# top_level.net
KiCad netlist of a schematic drawn in Altium Designer
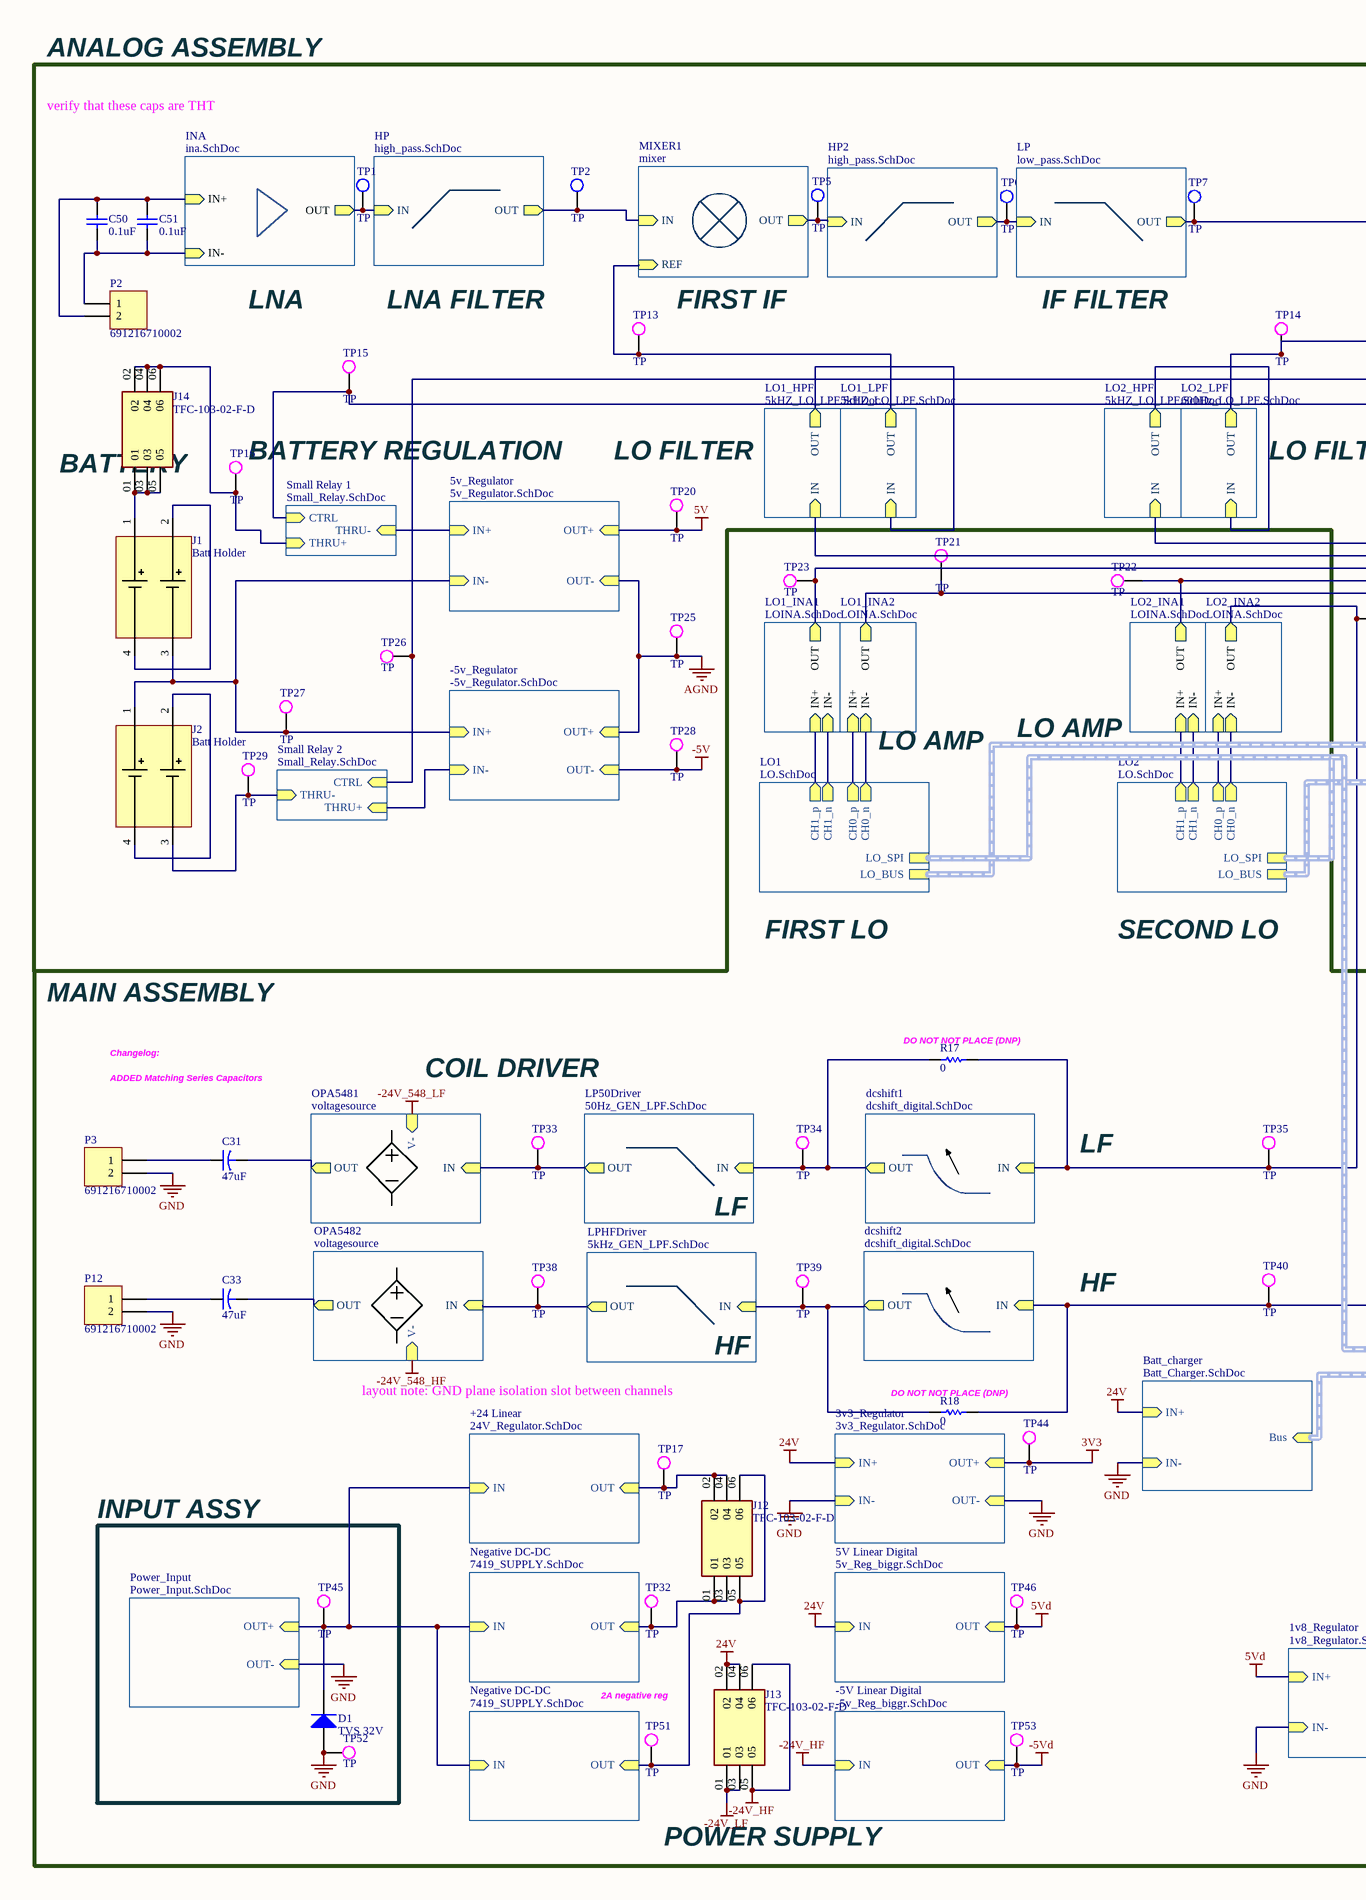
[diagram p0: top_level.SchDoc, left]
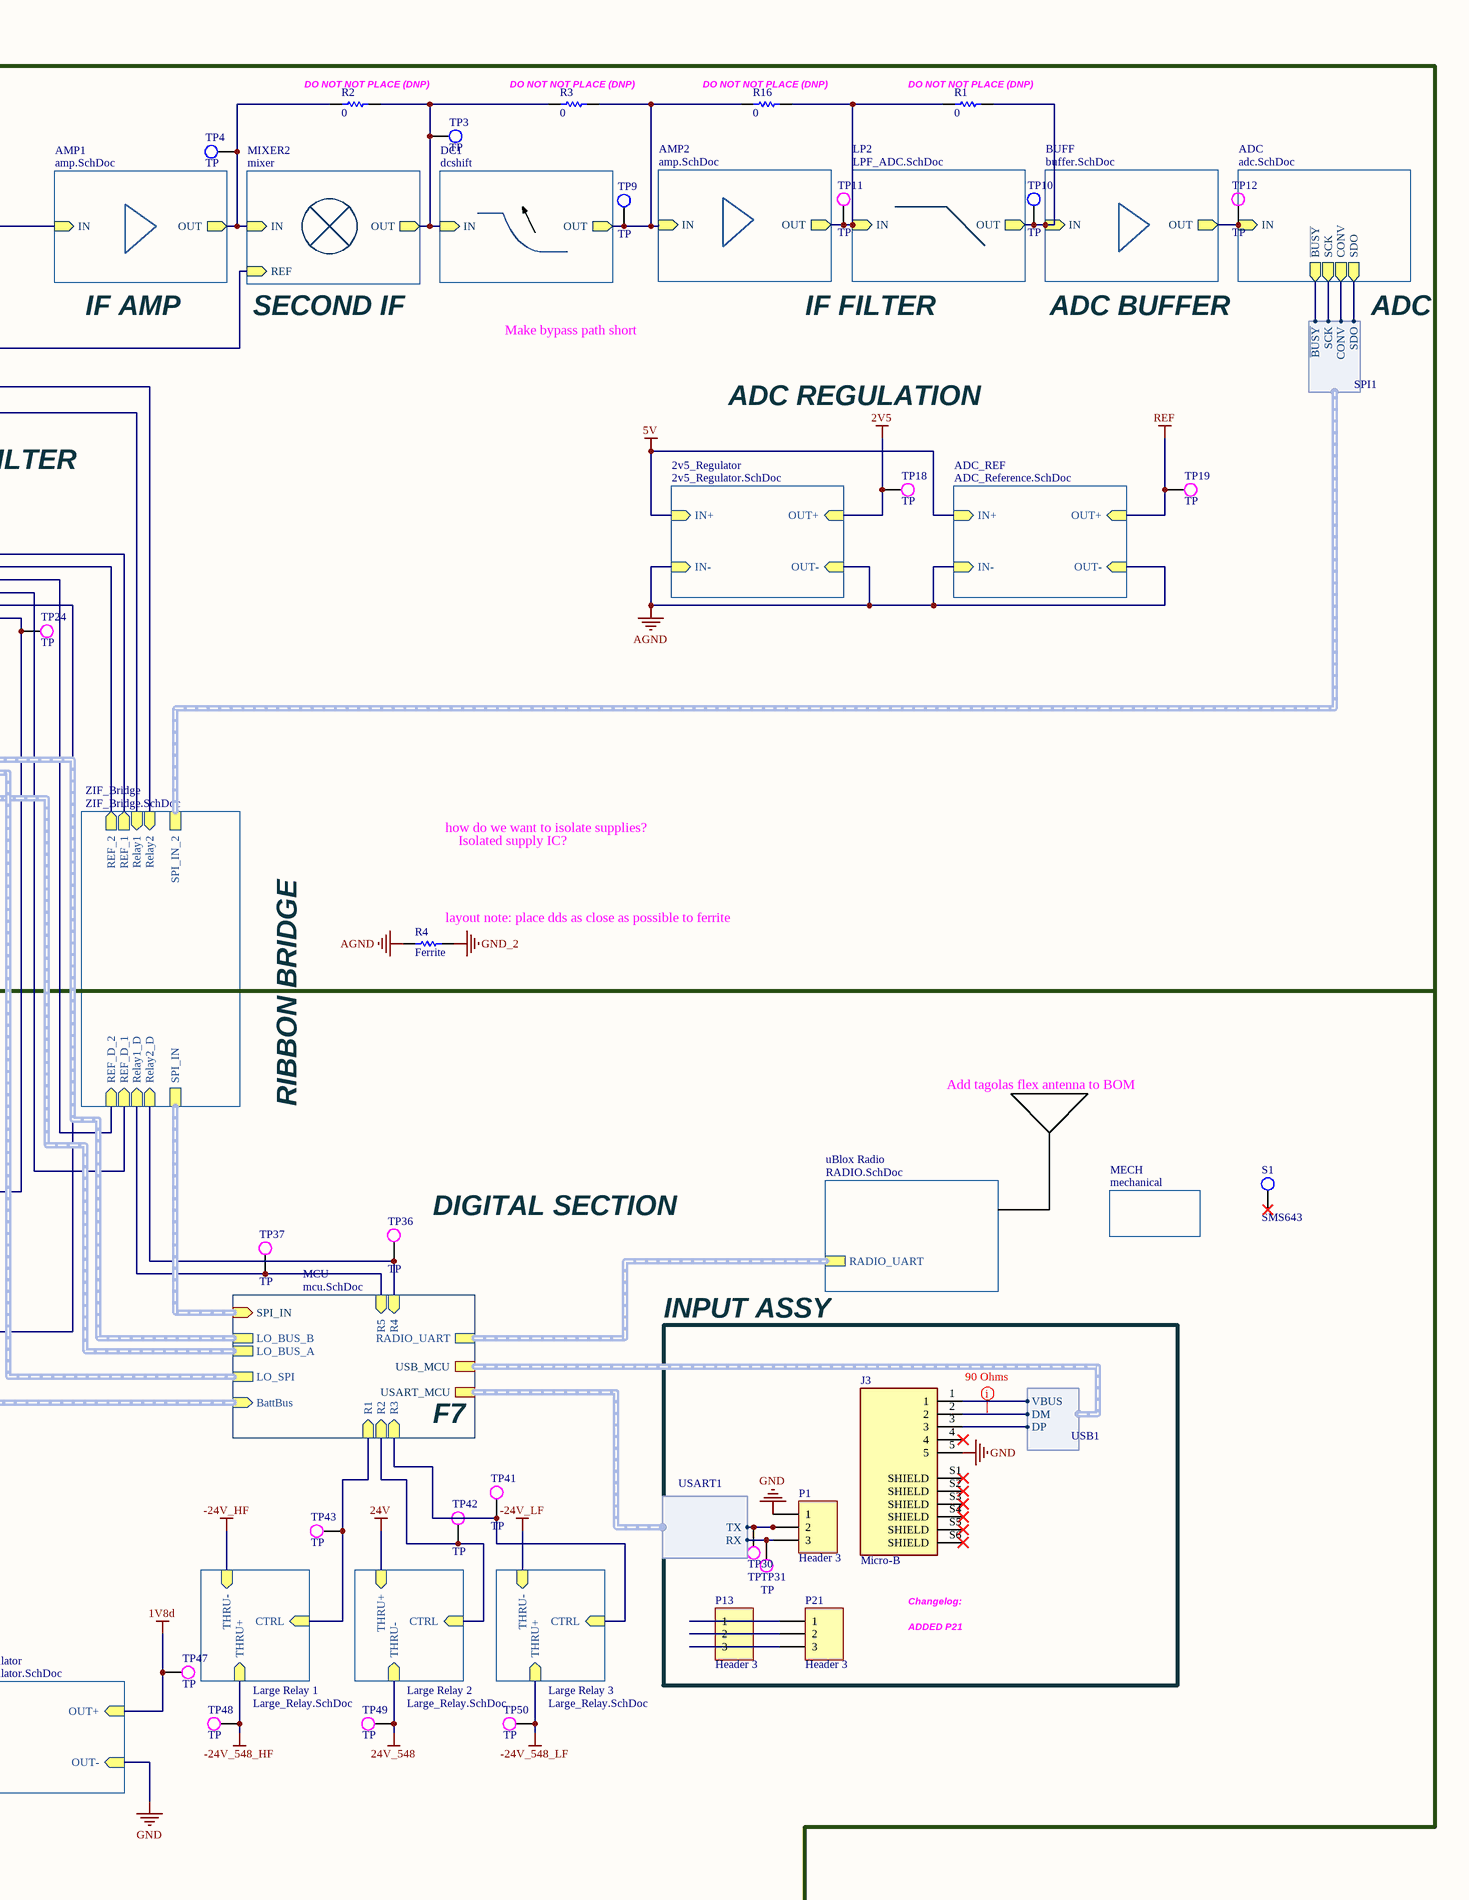
[diagram p1: top_level.SchDoc, right]

(export (version "E")
  (design (tool "Eeschema 10.0.6"))
  (components
    (comp (ref "C31")
      (value "47uF")
      (footprint "R60xW")
      (description "Capacitor, 47uF NICHICON")
      (libsource (lib "Arturo_Approved") (part "UCY2C470MPD"))
    )
    (comp (ref "C33")
      (value "47uF")
      (footprint "10uF_THT_Ceramic")
      (description "Capacitor, 47uF NICHICON")
      (libsource (lib "Arturo_Approved") (part "UCY2C470MPD"))
    )
    (comp (ref "C50")
      (value "0.1uF")
      (footprint "STD_0805_C")
      (description "Capacitor, 0.1uF, 0805")
      (libsource (lib "Arturo_Approved") (part "CL21B104KACNNNC"))
    )
    (comp (ref "C51")
      (value "0.1uF")
      (footprint "STD_0805_C")
      (description "Capacitor, 0.1uF, 0805")
      (libsource (lib "Arturo_Approved") (part "CL21B104KACNNNC"))
    )
    (comp (ref "D1")
      (value "TVS 32V")
      (footprint "TVSDIODE-DO214AA")
      (description "Default Diode")
      (fields (field (name "PUBLISHER") "Altium Limited"))
      (libsource (lib "Miscellaneous Devices") (part "Diode"))
    )
    (comp (ref "J1")
      (value "Batt Holder")
      (footprint "SMD_Batteryholder")
      (libsource (lib "Arturo_Approved") (part "1048_Keystone_18650"))
    )
    (comp (ref "J2")
      (value "Batt Holder")
      (footprint "SMD_Batteryholder")
      (libsource (lib "Arturo_Approved") (part "1048_Keystone_18650"))
    )
    (comp (ref "J3")
      (value "Micro-B")
      (footprint "10118194-0001LF")
      (description "USB - micro B USB 2.0 Receptacle Connector 5 Position Surface Mount, Right Angle; Through Hole")
      (libsource (lib "Arturo_Approved") (part "10118194-0001LF"))
    )
    (comp (ref "J12")
      (value "TFC-103-02-F-D")
      (footprint "Arturo_Approved:SAMTEC_TFC-103-02-F-D")
      (fields (field (name "MF") "Samtec"))
      (libsource (lib "Arturo_Approved") (part "TFC-103-02-F-D"))
    )
    (comp (ref "J13")
      (value "TFC-103-02-F-D")
      (footprint "Arturo_Approved:SAMTEC_TFC-103-02-F-D")
      (fields (field (name "MF") "Samtec"))
      (libsource (lib "Arturo_Approved") (part "TFC-103-02-F-D"))
    )
    (comp (ref "J14")
      (value "TFC-103-02-F-D")
      (footprint "Arturo_Approved:SAMTEC_TFC-103-02-F-D")
      (fields (field (name "MF") "Samtec"))
      (libsource (lib "Arturo_Approved") (part "TFC-103-02-F-D"))
    )
    (comp (ref "P1")
      (value "Header 3")
      (footprint "HDR1X3")
      (description "Header, 3-Pin")
      (fields (field (name "PUBLISHER") "Altium Limited"))
      (libsource (lib "Miscellaneous Connectors") (part "Header 3"))
    )
    (comp (ref "P2")
      (value "691216710002")
      (footprint "HDR1X2")
      (description "Header, 2-Pin")
      (fields (field (name "PUBLISHER") "Altium Limited"))
      (libsource (lib "") (part "Header 2_1"))
    )
    (comp (ref "P3")
      (value "691216710002")
      (footprint "HDR1X2")
      (description "Header, 2-Pin")
      (fields (field (name "PUBLISHER") "Altium Limited"))
      (libsource (lib "Miscellaneous Connectors") (part "Header 2"))
    )
    (comp (ref "P12")
      (value "691216710002")
      (footprint "HDR1X2")
      (description "Header, 2-Pin")
      (fields (field (name "PUBLISHER") "Altium Limited"))
      (libsource (lib "Miscellaneous Connectors") (part "Header 2"))
    )
    (comp (ref "P13")
      (value "Header 3")
      (footprint "HDR1X3")
      (description "Header, 3-Pin")
      (fields (field (name "PUBLISHER") "Altium Limited"))
      (libsource (lib "Miscellaneous Connectors") (part "Header 3"))
    )
    (comp (ref "P21")
      (value "Header 3")
      (footprint "HDR1X3")
      (description "Header, 3-Pin")
      (fields (field (name "PUBLISHER") "Altium Limited"))
      (libsource (lib "Miscellaneous Connectors") (part "Header 3"))
    )
    (comp (ref "R1")
      (value "0")
      (footprint "0402_Res")
      (description "0 ohm jumper")
      (libsource (lib "Arturo_Approved") (part "RMCF0805ZT0R00"))
    )
    (comp (ref "R2")
      (value "0")
      (footprint "0402_Res")
      (description "0 ohm jumper")
      (libsource (lib "Arturo_Approved") (part "RMCF0805ZT0R00"))
    )
    (comp (ref "R3")
      (value "0")
      (footprint "0402_Res")
      (description "0 ohm jumper")
      (libsource (lib "Arturo_Approved") (part "RMCF0805ZT0R00"))
    )
    (comp (ref "R4")
      (value "Ferrite")
      (footprint "0402_Res")
      (description "Ferrite 0805")
      (libsource (lib "Arturo_Approved") (part "BMB2A0600AN4"))
    )
    (comp (ref "R16")
      (value "0")
      (footprint "0402_Res")
      (description "0 ohm jumper")
      (libsource (lib "Arturo_Approved") (part "RMCF0805ZT0R00"))
    )
    (comp (ref "R17")
      (value "0")
      (footprint "0402_Res")
      (description "0 ohm jumper")
      (libsource (lib "Arturo_Approved") (part "RMCF0805ZT0R00"))
    )
    (comp (ref "R18")
      (value "0")
      (footprint "0402_Res")
      (description "0 ohm jumper")
      (libsource (lib "Arturo_Approved") (part "RMCF0805ZT0R00"))
    )
    (comp (ref "S1")
      (value "SMS643")
      (footprint "SMS-463F")
      (libsource (lib "Arturo_Approved") (part "SMS643"))
    )
    (comp (ref "TP1")
      (value "TP")
      (footprint "Test_point")
      (description "Test Point")
      (libsource (lib "Arturo_Approved") (part "TP"))
    )
    (comp (ref "TP2")
      (value "TP")
      (footprint "Test_point")
      (description "Test Point")
      (libsource (lib "Arturo_Approved") (part "TP"))
    )
    (comp (ref "TP3")
      (value "TP")
      (footprint "Test_point")
      (description "Test Point")
      (libsource (lib "Arturo_Approved") (part "TP"))
    )
    (comp (ref "TP4")
      (value "TP")
      (footprint "Test_point")
      (description "Test Point")
      (libsource (lib "Arturo_Approved") (part "TP"))
    )
    (comp (ref "TP5")
      (value "TP")
      (footprint "Test_point")
      (description "Test Point")
      (libsource (lib "Arturo_Approved") (part "TP"))
    )
    (comp (ref "TP6")
      (value "TP")
      (footprint "Test_point")
      (description "Test Point")
      (libsource (lib "Arturo_Approved") (part "TP"))
    )
    (comp (ref "TP7")
      (value "TP")
      (footprint "Test_point")
      (description "Test Point")
      (libsource (lib "Arturo_Approved") (part "TP"))
    )
    (comp (ref "TP9")
      (value "TP")
      (footprint "Test_point")
      (description "Test Point")
      (libsource (lib "Arturo_Approved") (part "TP"))
    )
    (comp (ref "TP10")
      (value "TP")
      (footprint "Test_point")
      (description "Test Point")
      (libsource (lib "Arturo_Approved") (part "TP"))
    )
    (comp (ref "TP11")
      (value "TP")
      (footprint "Test_point")
      (description "Test Point")
      (libsource (lib "Arturo_Approved") (part "TP_PCB"))
    )
    (comp (ref "TP12")
      (value "TP")
      (footprint "Test_point")
      (description "Test Point")
      (libsource (lib "Arturo_Approved") (part "TP_PCB"))
    )
    (comp (ref "TP13")
      (value "TP")
      (footprint "Test_point")
      (description "Test Point")
      (libsource (lib "Arturo_Approved") (part "TP_PCB"))
    )
    (comp (ref "TP14")
      (value "TP")
      (footprint "Test_point")
      (description "Test Point")
      (libsource (lib "Arturo_Approved") (part "TP_PCB"))
    )
    (comp (ref "TP15")
      (value "TP")
      (footprint "Test_point")
      (description "Test Point")
      (libsource (lib "Arturo_Approved") (part "TP_PCB"))
    )
    (comp (ref "TP16")
      (value "TP")
      (footprint "Test_point")
      (description "Test Point")
      (libsource (lib "Arturo_Approved") (part "TP_PCB"))
    )
    (comp (ref "TP17")
      (value "TP")
      (footprint "Test_point")
      (description "Test Point")
      (libsource (lib "Arturo_Approved") (part "TP_PCB"))
    )
    (comp (ref "TP18")
      (value "TP")
      (footprint "Test_point")
      (description "Test Point")
      (libsource (lib "Arturo_Approved") (part "TP_PCB"))
    )
    (comp (ref "TP19")
      (value "TP")
      (footprint "Test_point")
      (description "Test Point")
      (libsource (lib "Arturo_Approved") (part "TP_PCB"))
    )
    (comp (ref "TP20")
      (value "TP")
      (footprint "Test_point")
      (description "Test Point")
      (libsource (lib "Arturo_Approved") (part "TP_PCB"))
    )
    (comp (ref "TP21")
      (value "TP")
      (footprint "Test_point")
      (description "Test Point")
      (libsource (lib "Arturo_Approved") (part "TP_PCB"))
    )
    (comp (ref "TP22")
      (value "TP")
      (footprint "Test_point")
      (description "Test Point")
      (libsource (lib "Arturo_Approved") (part "TP_PCB"))
    )
    (comp (ref "TP23")
      (value "TP")
      (footprint "Test_point")
      (description "Test Point")
      (libsource (lib "Arturo_Approved") (part "TP_PCB"))
    )
    (comp (ref "TP24")
      (value "TP")
      (footprint "Test_point")
      (description "Test Point")
      (libsource (lib "Arturo_Approved") (part "TP_PCB"))
    )
    (comp (ref "TP25")
      (value "TP")
      (footprint "Test_point")
      (description "Test Point")
      (libsource (lib "Arturo_Approved") (part "TP_PCB"))
    )
    (comp (ref "TP26")
      (value "TP")
      (footprint "Test_point")
      (description "Test Point")
      (libsource (lib "Arturo_Approved") (part "TP_PCB"))
    )
    (comp (ref "TP27")
      (value "TP")
      (footprint "Test_point")
      (description "Test Point")
      (libsource (lib "Arturo_Approved") (part "TP_PCB"))
    )
    (comp (ref "TP28")
      (value "TP")
      (footprint "Test_point")
      (description "Test Point")
      (libsource (lib "Arturo_Approved") (part "TP_PCB"))
    )
    (comp (ref "TP29")
      (value "TP")
      (footprint "Test_point")
      (description "Test Point")
      (libsource (lib "Arturo_Approved") (part "TP_PCB"))
    )
    (comp (ref "TP30")
      (value "TP")
      (footprint "Test_point")
      (description "Test Point")
      (libsource (lib "Arturo_Approved") (part "TP_PCB"))
    )
    (comp (ref "TP31")
      (value "TP")
      (footprint "Test_point")
      (description "Test Point")
      (libsource (lib "Arturo_Approved") (part "TP_PCB"))
    )
    (comp (ref "TP32")
      (value "TP")
      (footprint "Test_point")
      (description "Test Point")
      (libsource (lib "Arturo_Approved") (part "TP_PCB"))
    )
    (comp (ref "TP33")
      (value "TP")
      (footprint "Test_point")
      (description "Test Point")
      (libsource (lib "Arturo_Approved") (part "TP_PCB"))
    )
    (comp (ref "TP34")
      (value "TP")
      (footprint "Test_point")
      (description "Test Point")
      (libsource (lib "Arturo_Approved") (part "TP_PCB"))
    )
    (comp (ref "TP35")
      (value "TP")
      (footprint "Test_point")
      (description "Test Point")
      (libsource (lib "Arturo_Approved") (part "TP_PCB"))
    )
    (comp (ref "TP36")
      (value "TP")
      (footprint "Test_point")
      (description "Test Point")
      (libsource (lib "Arturo_Approved") (part "TP_PCB"))
    )
    (comp (ref "TP37")
      (value "TP")
      (footprint "Test_point")
      (description "Test Point")
      (libsource (lib "Arturo_Approved") (part "TP_PCB"))
    )
    (comp (ref "TP38")
      (value "TP")
      (footprint "Test_point")
      (description "Test Point")
      (libsource (lib "Arturo_Approved") (part "TP_PCB"))
    )
    (comp (ref "TP39")
      (value "TP")
      (footprint "Test_point")
      (description "Test Point")
      (libsource (lib "Arturo_Approved") (part "TP_PCB"))
    )
    (comp (ref "TP40")
      (value "TP")
      (footprint "Test_point")
      (description "Test Point")
      (libsource (lib "Arturo_Approved") (part "TP_PCB"))
    )
    (comp (ref "TP41")
      (value "TP")
      (footprint "Test_point")
      (description "Test Point")
      (libsource (lib "Arturo_Approved") (part "TP_PCB"))
    )
    (comp (ref "TP42")
      (value "TP")
      (footprint "Test_point")
      (description "Test Point")
      (libsource (lib "Arturo_Approved") (part "TP_PCB"))
    )
    (comp (ref "TP43")
      (value "TP")
      (footprint "Test_point")
      (description "Test Point")
      (libsource (lib "Arturo_Approved") (part "TP_PCB"))
    )
    (comp (ref "TP44")
      (value "TP")
      (footprint "Test_point")
      (description "Test Point")
      (libsource (lib "Arturo_Approved") (part "TP_PCB"))
    )
    (comp (ref "TP45")
      (value "TP")
      (footprint "Test_point")
      (description "Test Point")
      (libsource (lib "Arturo_Approved") (part "TP_PCB"))
    )
    (comp (ref "TP46")
      (value "TP")
      (footprint "Test_point")
      (description "Test Point")
      (libsource (lib "Arturo_Approved") (part "TP_PCB"))
    )
    (comp (ref "TP47")
      (value "TP")
      (footprint "Test_point")
      (description "Test Point")
      (libsource (lib "Arturo_Approved") (part "TP_PCB"))
    )
    (comp (ref "TP48")
      (value "TP")
      (footprint "Test_point")
      (description "Test Point")
      (libsource (lib "Arturo_Approved") (part "TP_PCB"))
    )
    (comp (ref "TP49")
      (value "TP")
      (footprint "Test_point")
      (description "Test Point")
      (libsource (lib "Arturo_Approved") (part "TP_PCB"))
    )
    (comp (ref "TP50")
      (value "TP")
      (footprint "Test_point")
      (description "Test Point")
      (libsource (lib "Arturo_Approved") (part "TP_PCB"))
    )
    (comp (ref "TP51")
      (value "TP")
      (footprint "Test_point")
      (description "Test Point")
      (libsource (lib "Arturo_Approved") (part "TP_PCB"))
    )
    (comp (ref "TP52")
      (value "TP")
      (footprint "Test_point")
      (description "Test Point")
      (libsource (lib "Arturo_Approved") (part "TP_PCB"))
    )
    (comp (ref "TP53")
      (value "TP")
      (footprint "Test_point")
      (description "Test Point")
      (libsource (lib "Arturo_Approved") (part "TP_PCB"))
    )
  )
  (nets
    (net (code "4") (name "-5V") (class "Default")
      (node (ref "TP28") (pin "1") (pinfunction "1_1") (pintype "passive"))
    )
    (net (code "5") (name "-5Vd") (class "Default")
      (node (ref "TP53") (pin "1") (pinfunction "1_1") (pintype "passive"))
    )
    (net (code "6") (name "-24V_548_HF") (class "Default")
      (node (ref "TP48") (pin "1") (pinfunction "1_1") (pintype "passive"))
    )
    (net (code "7") (name "-24V_548_LF") (class "Default")
      (node (ref "TP50") (pin "1") (pinfunction "1_1") (pintype "passive"))
    )
    (net (code "8") (name "-24V_HF") (class "Default")
      (node (ref "J13") (pin "05") (pinfunction "05_05") (pintype "passive"))
      (node (ref "J13") (pin "06") (pinfunction "06_06") (pintype "passive"))
    )
    (net (code "9") (name "-24V_LF") (class "Default")
      (node (ref "J13") (pin "01") (pinfunction "01_01") (pintype "passive"))
      (node (ref "J13") (pin "03") (pinfunction "03_03") (pintype "passive"))
    )
    (net (code "20") (name "/CTRL") (class "Default")
      (node (ref "TP26") (pin "1") (pinfunction "1_1") (pintype "passive"))
    )
    (net (code "21") (name "/CTRL_1") (class "Default")
      (node (ref "TP43") (pin "1") (pinfunction "1_1") (pintype "passive"))
    )
    (net (code "22") (name "/CTRL_2") (class "Default")
      (node (ref "TP42") (pin "1") (pinfunction "1_1") (pintype "passive"))
    )
    (net (code "23") (name "/CTRL_3") (class "Default")
      (node (ref "TP41") (pin "1") (pinfunction "1_1") (pintype "passive"))
    )
    (net (code "24") (name "/CTRL_4") (class "Default")
      (node (ref "TP15") (pin "1") (pinfunction "1_1") (pintype "passive"))
    )
    (net (code "25") (name "/IN") (class "Default")
      (node (ref "D1") (pin "2") (pinfunction "K_2") (pintype "passive"))
      (node (ref "TP45") (pin "1") (pinfunction "1_1") (pintype "passive"))
    )
    (net (code "27") (name "/IN+_1") (class "Default")
      (node (ref "C50") (pin "2") (pinfunction "2_2") (pintype "passive"))
      (node (ref "C51") (pin "2") (pinfunction "2_2") (pintype "passive"))
      (node (ref "P2") (pin "2") (pinfunction "2_2") (pintype "passive"))
    )
    (net (code "28") (name "/IN+_2") (class "Default")
      (node (ref "J1") (pin "3") (pinfunction "3_3") (pintype "passive"))
      (node (ref "J2") (pin "1") (pinfunction "1_1") (pintype "passive"))
      (node (ref "TP27") (pin "1") (pinfunction "1_1") (pintype "passive"))
    )
    (net (code "30") (name "/IN-_1") (class "Default")
      (node (ref "C50") (pin "1") (pinfunction "1_1") (pintype "passive"))
      (node (ref "C51") (pin "1") (pinfunction "1_1") (pintype "passive"))
      (node (ref "P2") (pin "1") (pinfunction "1_1") (pintype "passive"))
    )
    (net (code "34") (name "/OUT") (class "Default")
      (node (ref "R1") (pin "2") (pinfunction "2_2") (pintype "passive"))
      (node (ref "TP10") (pin "1") (pinfunction "1_1") (pintype "passive"))
    )
    (net (code "35") (name "/OUT_1") (class "Default")
      (node (ref "R2") (pin "1") (pinfunction "1_1") (pintype "passive"))
      (node (ref "TP4") (pin "1") (pinfunction "1_1") (pintype "passive"))
    )
    (net (code "36") (name "/OUT_2") (class "Default")
      (node (ref "R2") (pin "2") (pinfunction "2_2") (pintype "passive"))
      (node (ref "R3") (pin "1") (pinfunction "1_1") (pintype "passive"))
      (node (ref "TP3") (pin "1") (pinfunction "1_1") (pintype "passive"))
    )
    (net (code "37") (name "/OUT_3") (class "Default")
      (node (ref "R16") (pin "1") (pinfunction "1_1") (pintype "passive"))
      (node (ref "R3") (pin "2") (pinfunction "2_2") (pintype "passive"))
      (node (ref "TP9") (pin "1") (pinfunction "1_1") (pintype "passive"))
    )
    (net (code "38") (name "/OUT_4") (class "Default")
      (node (ref "TP23") (pin "1") (pinfunction "1_1") (pintype "passive"))
    )
    (net (code "39") (name "/OUT_5") (class "Default")
      (node (ref "R17") (pin "2") (pinfunction "2_2") (pintype "passive"))
      (node (ref "TP24") (pin "1") (pinfunction "1_1") (pintype "passive"))
      (node (ref "TP35") (pin "1") (pinfunction "1_1") (pintype "passive"))
    )
    (net (code "40") (name "/OUT_6") (class "Default")
      (node (ref "TP22") (pin "1") (pinfunction "1_1") (pintype "passive"))
    )
    (net (code "41") (name "/OUT_7") (class "Default")
      (node (ref "R18") (pin "2") (pinfunction "2_2") (pintype "passive"))
      (node (ref "TP21") (pin "1") (pinfunction "1_1") (pintype "passive"))
      (node (ref "TP40") (pin "1") (pinfunction "1_1") (pintype "passive"))
    )
    (net (code "42") (name "/OUT_8") (class "Default")
      (node (ref "R17") (pin "1") (pinfunction "1_1") (pintype "passive"))
      (node (ref "TP34") (pin "1") (pinfunction "1_1") (pintype "passive"))
    )
    (net (code "43") (name "/OUT_9") (class "Default")
      (node (ref "R18") (pin "1") (pinfunction "1_1") (pintype "passive"))
      (node (ref "TP39") (pin "1") (pinfunction "1_1") (pintype "passive"))
    )
    (net (code "44") (name "/OUT_10") (class "Default")
      (node (ref "TP14") (pin "1") (pinfunction "1_1") (pintype "passive"))
    )
    (net (code "45") (name "/OUT_11") (class "Default")
      (node (ref "TP5") (pin "1") (pinfunction "1_1") (pintype "passive"))
    )
    (net (code "46") (name "/OUT_12") (class "Default")
      (node (ref "TP6") (pin "1") (pinfunction "1_1") (pintype "passive"))
    )
    (net (code "47") (name "/OUT_13") (class "Default")
      (node (ref "TP7") (pin "1") (pinfunction "1_1") (pintype "passive"))
    )
    (net (code "49") (name "/OUT_15") (class "Default")
      (node (ref "TP1") (pin "1") (pinfunction "1_1") (pintype "passive"))
    )
    (net (code "50") (name "/OUT_16") (class "Default")
      (node (ref "TP2") (pin "1") (pinfunction "1_1") (pintype "passive"))
    )
    (net (code "51") (name "/OUT_17") (class "Default")
      (node (ref "TP13") (pin "1") (pinfunction "1_1") (pintype "passive"))
    )
    (net (code "53") (name "/OUT_19") (class "Default")
      (node (ref "R1") (pin "1") (pinfunction "1_1") (pintype "passive"))
      (node (ref "R16") (pin "2") (pinfunction "2_2") (pintype "passive"))
      (node (ref "TP11") (pin "1") (pinfunction "1_1") (pintype "passive"))
    )
    (net (code "54") (name "/OUT_20") (class "Default")
      (node (ref "J12") (pin "05") (pinfunction "05_05") (pintype "passive"))
      (node (ref "J12") (pin "06") (pinfunction "06_06") (pintype "passive"))
      (node (ref "TP51") (pin "1") (pinfunction "1_1") (pintype "passive"))
    )
    (net (code "55") (name "/OUT_21") (class "Default")
      (node (ref "J12") (pin "01") (pinfunction "01_01") (pintype "passive"))
      (node (ref "J12") (pin "03") (pinfunction "03_03") (pintype "passive"))
      (node (ref "TP32") (pin "1") (pinfunction "1_1") (pintype "passive"))
    )
    (net (code "56") (name "/OUT_22") (class "Default")
      (node (ref "J12") (pin "02") (pinfunction "02_02") (pintype "passive"))
      (node (ref "J12") (pin "04") (pinfunction "04_04") (pintype "passive"))
      (node (ref "TP17") (pin "1") (pinfunction "1_1") (pintype "passive"))
    )
    (net (code "57") (name "/OUT_23") (class "Default")
      (node (ref "TP38") (pin "1") (pinfunction "1_1") (pintype "passive"))
    )
    (net (code "58") (name "/OUT_24") (class "Default")
      (node (ref "TP33") (pin "1") (pinfunction "1_1") (pintype "passive"))
    )
    (net (code "59") (name "/OUT_25") (class "Default")
      (node (ref "C33") (pin "2") (pinfunction "2_2") (pintype "passive"))
    )
    (net (code "60") (name "/OUT_26") (class "Default")
      (node (ref "C31") (pin "2") (pinfunction "2_2") (pintype "passive"))
    )
    (net (code "61") (name "/OUT_27") (class "Default")
      (node (ref "TP12") (pin "1") (pinfunction "1_1") (pintype "passive"))
    )
    (net (code "62") (name "/R4") (class "Default")
      (node (ref "TP36") (pin "1") (pinfunction "1_1") (pintype "passive"))
    )
    (net (code "63") (name "/R5") (class "Default")
      (node (ref "TP37") (pin "1") (pinfunction "1_1") (pintype "passive"))
    )
    (net (code "70") (name "/THRU+") (class "Default")
      (node (ref "J14") (pin "02") (pinfunction "02_02") (pintype "passive"))
      (node (ref "J14") (pin "04") (pinfunction "04_04") (pintype "passive"))
      (node (ref "J14") (pin "06") (pinfunction "06_06") (pintype "passive"))
      (node (ref "TP16") (pin "1") (pinfunction "1_1") (pintype "passive"))
    )
    (net (code "71") (name "/THRU-") (class "Default")
      (node (ref "J2") (pin "3") (pinfunction "3_3") (pintype "passive"))
      (node (ref "TP29") (pin "1") (pinfunction "1_1") (pintype "passive"))
    )
    (net (code "76") (name "1V8d") (class "Default")
      (node (ref "TP47") (pin "1") (pinfunction "1_1") (pintype "passive"))
    )
    (net (code "77") (name "2V5") (class "Default")
      (node (ref "TP18") (pin "1") (pinfunction "1_1") (pintype "passive"))
    )
    (net (code "78") (name "3V3") (class "Default")
      (node (ref "TP44") (pin "1") (pinfunction "1_1") (pintype "passive"))
    )
    (net (code "79") (name "5V") (class "Default")
      (node (ref "TP20") (pin "1") (pinfunction "1_1") (pintype "passive"))
    )
    (net (code "80") (name "5Vd") (class "Default")
      (node (ref "TP46") (pin "1") (pinfunction "1_1") (pintype "passive"))
    )
    (net (code "81") (name "24V") (class "Default")
      (node (ref "J13") (pin "02") (pinfunction "02_02") (pintype "passive"))
      (node (ref "J13") (pin "04") (pinfunction "04_04") (pintype "passive"))
    )
    (net (code "82") (name "24V_548") (class "Default")
      (node (ref "TP49") (pin "1") (pinfunction "1_1") (pintype "passive"))
    )
    (net (code "83") (name "AGND") (class "Default")
      (node (ref "R4") (pin "1") (pinfunction "1_1") (pintype "passive"))
      (node (ref "TP25") (pin "1") (pinfunction "1_1") (pintype "passive"))
    )
    (net (code "84") (name "GND") (class "Default")
      (node (ref "D1") (pin "1") (pinfunction "A_1") (pintype "passive"))
      (node (ref "J3") (pin "5") (pinfunction "5_5") (pintype "passive"))
      (node (ref "P1") (pin "1") (pinfunction "1_1") (pintype "passive"))
      (node (ref "P12") (pin "2") (pinfunction "2_2") (pintype "passive"))
      (node (ref "P3") (pin "2") (pinfunction "2_2") (pintype "passive"))
      (node (ref "TP52") (pin "1") (pinfunction "1_1") (pintype "passive"))
    )
    (net (code "85") (name "GND_2") (class "Default")
      (node (ref "R4") (pin "2") (pinfunction "2_2") (pintype "passive"))
    )
    (net (code "86") (name "Net-(C31-Pad1)") (class "Default")
      (node (ref "C31") (pin "1") (pinfunction "1_1") (pintype "passive"))
      (node (ref "P3") (pin "1") (pinfunction "1_1") (pintype "passive"))
    )
    (net (code "87") (name "Net-(C33-Pad1)") (class "Default")
      (node (ref "C33") (pin "1") (pinfunction "1_1") (pintype "passive"))
      (node (ref "P12") (pin "1") (pinfunction "1_1") (pintype "passive"))
    )
    (net (code "88") (name "Net-(J1-Pad1)") (class "Default")
      (node (ref "J1") (pin "1") (pinfunction "1_1") (pintype "passive"))
      (node (ref "J14") (pin "01") (pinfunction "01_01") (pintype "passive"))
      (node (ref "J14") (pin "03") (pinfunction "03_03") (pintype "passive"))
      (node (ref "J14") (pin "05") (pinfunction "05_05") (pintype "passive"))
    )
    (net (code "89") (name "Net-(J1-Pad2)") (class "Default")
      (node (ref "J1") (pin "2") (pinfunction "2_2") (pintype "passive"))
      (node (ref "J1") (pin "4") (pinfunction "4_4") (pintype "passive"))
    )
    (net (code "90") (name "Net-(J2-Pad2)") (class "Default")
      (node (ref "J2") (pin "2") (pinfunction "2_2") (pintype "passive"))
      (node (ref "J2") (pin "4") (pinfunction "4_4") (pintype "passive"))
    )
    (net (code "91") (name "Net-(P1-Pad2)") (class "Default")
      (node (ref "P1") (pin "2") (pinfunction "2_2") (pintype "passive"))
      (node (ref "TP30") (pin "1") (pinfunction "1_1") (pintype "passive"))
    )
    (net (code "92") (name "Net-(P1-Pad3)") (class "Default")
      (node (ref "P1") (pin "3") (pinfunction "3_3") (pintype "passive"))
      (node (ref "TP31") (pin "1") (pinfunction "1_1") (pintype "passive"))
    )
    (net (code "93") (name "Net-(P13-Pad1)") (class "Default")
      (node (ref "P13") (pin "1") (pinfunction "1_1") (pintype "passive"))
      (node (ref "P21") (pin "1") (pinfunction "1_1") (pintype "passive"))
    )
    (net (code "94") (name "Net-(P13-Pad2)") (class "Default")
      (node (ref "P13") (pin "2") (pinfunction "2_2") (pintype "passive"))
      (node (ref "P21") (pin "2") (pinfunction "2_2") (pintype "passive"))
    )
    (net (code "95") (name "Net-(P13-Pad3)") (class "Default")
      (node (ref "P13") (pin "3") (pinfunction "3_3") (pintype "passive"))
      (node (ref "P21") (pin "3") (pinfunction "3_3") (pintype "passive"))
    )
    (net (code "96") (name "REF") (class "Default")
      (node (ref "TP19") (pin "1") (pinfunction "1_1") (pintype "passive"))
    )
    (net (code "97") (name "unconnected-(J3-Pad1)") (class "Default")
      (node (ref "J3") (pin "1") (pinfunction "1_1") (pintype "passive"))
    )
    (net (code "98") (name "unconnected-(J3-Pad2)") (class "Default")
      (node (ref "J3") (pin "2") (pinfunction "2_2") (pintype "passive"))
    )
    (net (code "99") (name "unconnected-(J3-Pad3)") (class "Default")
      (node (ref "J3") (pin "3") (pinfunction "3_3") (pintype "passive"))
    )
    (net (code "100") (name "unconnected-(J3-Pad4)") (class "Default")
      (node (ref "J3") (pin "4") (pinfunction "4_4") (pintype "passive+no_connect"))
    )
    (net (code "101") (name "unconnected-(J3-SHIELD-PadS1)") (class "Default")
      (node (ref "J3") (pin "S1") (pinfunction "SHIELD_S1") (pintype "passive+no_connect"))
    )
    (net (code "102") (name "unconnected-(J3-SHIELD-PadS2)") (class "Default")
      (node (ref "J3") (pin "S2") (pinfunction "SHIELD_S2") (pintype "passive+no_connect"))
    )
    (net (code "103") (name "unconnected-(J3-SHIELD-PadS3)") (class "Default")
      (node (ref "J3") (pin "S3") (pinfunction "SHIELD_S3") (pintype "passive+no_connect"))
    )
    (net (code "104") (name "unconnected-(J3-SHIELD-PadS4)") (class "Default")
      (node (ref "J3") (pin "S4") (pinfunction "SHIELD_S4") (pintype "passive+no_connect"))
    )
    (net (code "105") (name "unconnected-(J3-SHIELD-PadS5)") (class "Default")
      (node (ref "J3") (pin "S5") (pinfunction "SHIELD_S5") (pintype "passive+no_connect"))
    )
    (net (code "106") (name "unconnected-(J3-SHIELD-PadS6)") (class "Default")
      (node (ref "J3") (pin "S6") (pinfunction "SHIELD_S6") (pintype "passive+no_connect"))
    )
    (net (code "107") (name "unconnected-(S1-Pad1)") (class "Default")
      (node (ref "S1") (pin "1") (pinfunction "1_1") (pintype "passive+no_connect"))
    )
  )
)
